# pay-motors-prototype.net
KiCad netlist of a schematic drawn in Altium Designer
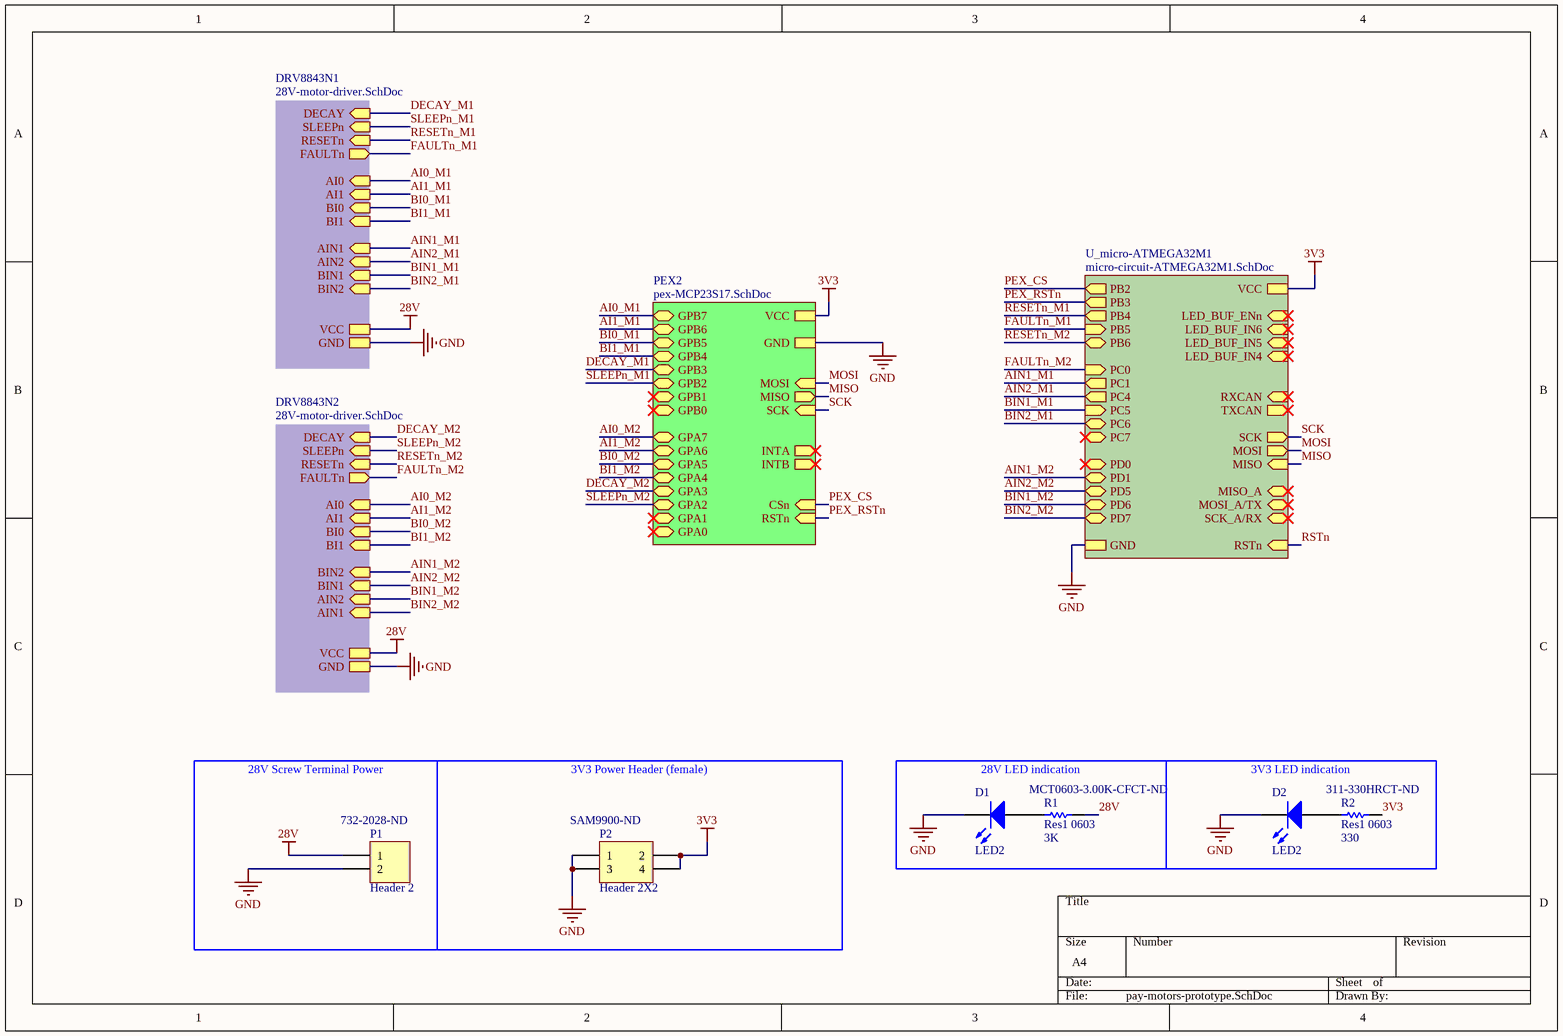
[diagram p0: pay-motors-prototype.SchDoc]

(export (version "E")
  (design (tool "Eeschema 10.0.6"))
  (components
    (comp (ref "D1")
      (value "LED2")
      (footprint "0603-LED")
      (description "Typical RED, GREEN, YELLOW, AMBER GaAs LED")
      (fields (field (name "PUBLISHER") "Altium Limited"))
      (libsource (lib "Miscellaneous Devices") (part "LED2"))
    )
    (comp (ref "D2")
      (value "LED2")
      (footprint "0603-LED")
      (description "Typical RED, GREEN, YELLOW, AMBER GaAs LED")
      (fields (field (name "PUBLISHER") "Altium Limited"))
      (libsource (lib "Miscellaneous Devices") (part "LED2"))
    )
    (comp (ref "P1")
      (value "Header 2")
      (footprint "CON2_SCREW_5.00MM_691102710002")
      (description "Header, 2-Pin")
      (fields
        (field (name "SUPPLIER PART NUMBER 1") "732-2028-ND")
        (field (name "PUBLISHER") "Altium Limited")
      )
      (libsource (lib "Miscellaneous Connectors") (part "Header 2"))
    )
    (comp (ref "P2")
      (value "Header 2X2")
      (footprint "HDR2X2")
      (description "Header, 2-Pin, Dual row")
      (fields
        (field (name "SUPPLIER PART NUMBER 1") "SAM9900-ND")
        (field (name "PUBLISHER") "Altium Limited")
      )
      (libsource (lib "Miscellaneous Connectors") (part "Header 2X2"))
    )
    (comp (ref "R1")
      (value "Res1 0603")
      (footprint "0603-RES")
      (description "Resistor")
      (fields
        (field (name "ALTIUM_VALUE") "3K")
        (field (name "SUPPLIER PART NUMBER 1") "MCT0603-3.00K-CFCT-ND")
        (field (name "PUBLISHER") "Altium Limited")
      )
      (libsource (lib "Miscellaneous Devices") (part "Res1"))
    )
    (comp (ref "R2")
      (value "Res1 0603")
      (footprint "0603-RES")
      (description "Resistor")
      (fields
        (field (name "ALTIUM_VALUE") "330")
        (field (name "SUPPLIER PART NUMBER 1") "311-330HRCT-ND")
        (field (name "PUBLISHER") "Altium Limited")
      )
      (libsource (lib "Miscellaneous Devices") (part "Res1"))
    )
  )
  (nets
    (net (code "48") (name "3V3") (class "Default")
      (node (ref "P2") (pin "2") (pinfunction "2_2") (pintype "passive"))
      (node (ref "P2") (pin "4") (pinfunction "4_4") (pintype "passive"))
      (node (ref "R2") (pin "2") (pinfunction "2_2") (pintype "passive"))
    )
    (net (code "49") (name "28V") (class "Default")
      (node (ref "P1") (pin "1") (pinfunction "1_1") (pintype "passive"))
      (node (ref "R1") (pin "2") (pinfunction "2_2") (pintype "passive"))
    )
    (net (code "50") (name "GND") (class "Default")
      (node (ref "D1") (pin "2") (pinfunction "K_2") (pintype "passive"))
      (node (ref "D2") (pin "2") (pinfunction "K_2") (pintype "passive"))
      (node (ref "P1") (pin "2") (pinfunction "2_2") (pintype "passive"))
      (node (ref "P2") (pin "1") (pinfunction "1_1") (pintype "passive"))
      (node (ref "P2") (pin "3") (pinfunction "3_3") (pintype "passive"))
    )
    (net (code "51") (name "Net-(D1-A)") (class "Default")
      (node (ref "D1") (pin "1") (pinfunction "A_1") (pintype "passive"))
      (node (ref "R1") (pin "1") (pinfunction "1_1") (pintype "passive"))
    )
    (net (code "52") (name "Net-(D2-A)") (class "Default")
      (node (ref "D2") (pin "1") (pinfunction "A_1") (pintype "passive"))
      (node (ref "R2") (pin "1") (pinfunction "1_1") (pintype "passive"))
    )
  )
)
